# Toggle.net
KiCad netlist of a schematic drawn in Altium Designer
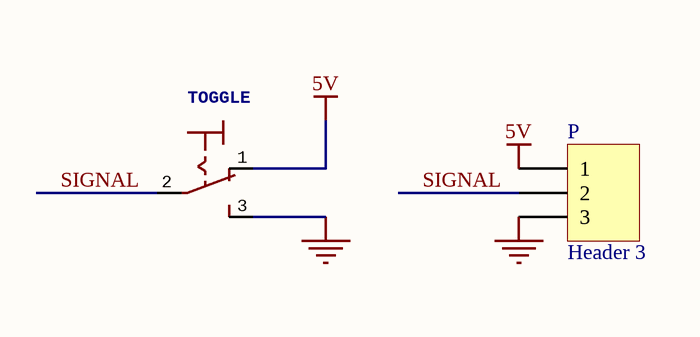
[diagram p0: Toggle.SchDoc]

(export (version "E")
  (design (tool "Eeschema 10.0.6"))
  (components
    (comp (ref "P")
      (value "Header 3")
      (footprint "B3B-PH-K-S(LF)(SN)")
      (description "CONN HEADER VERT 3POS 2MM")
      (fields (field (name "PUBLISHER") "Altium Limited"))
      (libsource (lib "Miscellaneous Connectors") (part "Header 3"))
    )
    (comp (ref "TOGGLE")
      (value "5636AB9")
      (footprint "320-916")
      (description "SWITCH TOGGLE SPDT 6A 125V")
      (libsource (lib "Schlib") (part "320-916"))
    )
  )
  (nets
    (net (code "1") (name "/SIGNAL") (class "Default")
      (node (ref "P") (pin "2") (pinfunction "2_2") (pintype "passive"))
      (node (ref "TOGGLE") (pin "2") (pinfunction "P_2") (pintype "passive"))
    )
    (net (code "2") (name "5V") (class "Default")
      (node (ref "P") (pin "1") (pinfunction "1_1") (pintype "passive"))
      (node (ref "TOGGLE") (pin "1") (pinfunction "O_1") (pintype "passive"))
    )
    (net (code "3") (name "GND") (class "Default")
      (node (ref "P") (pin "3") (pinfunction "3_3") (pintype "passive"))
      (node (ref "TOGGLE") (pin "3") (pinfunction "S_3") (pintype "passive"))
    )
  )
)
